# Lights.net
KiCad netlist of a schematic drawn in Altium Designer
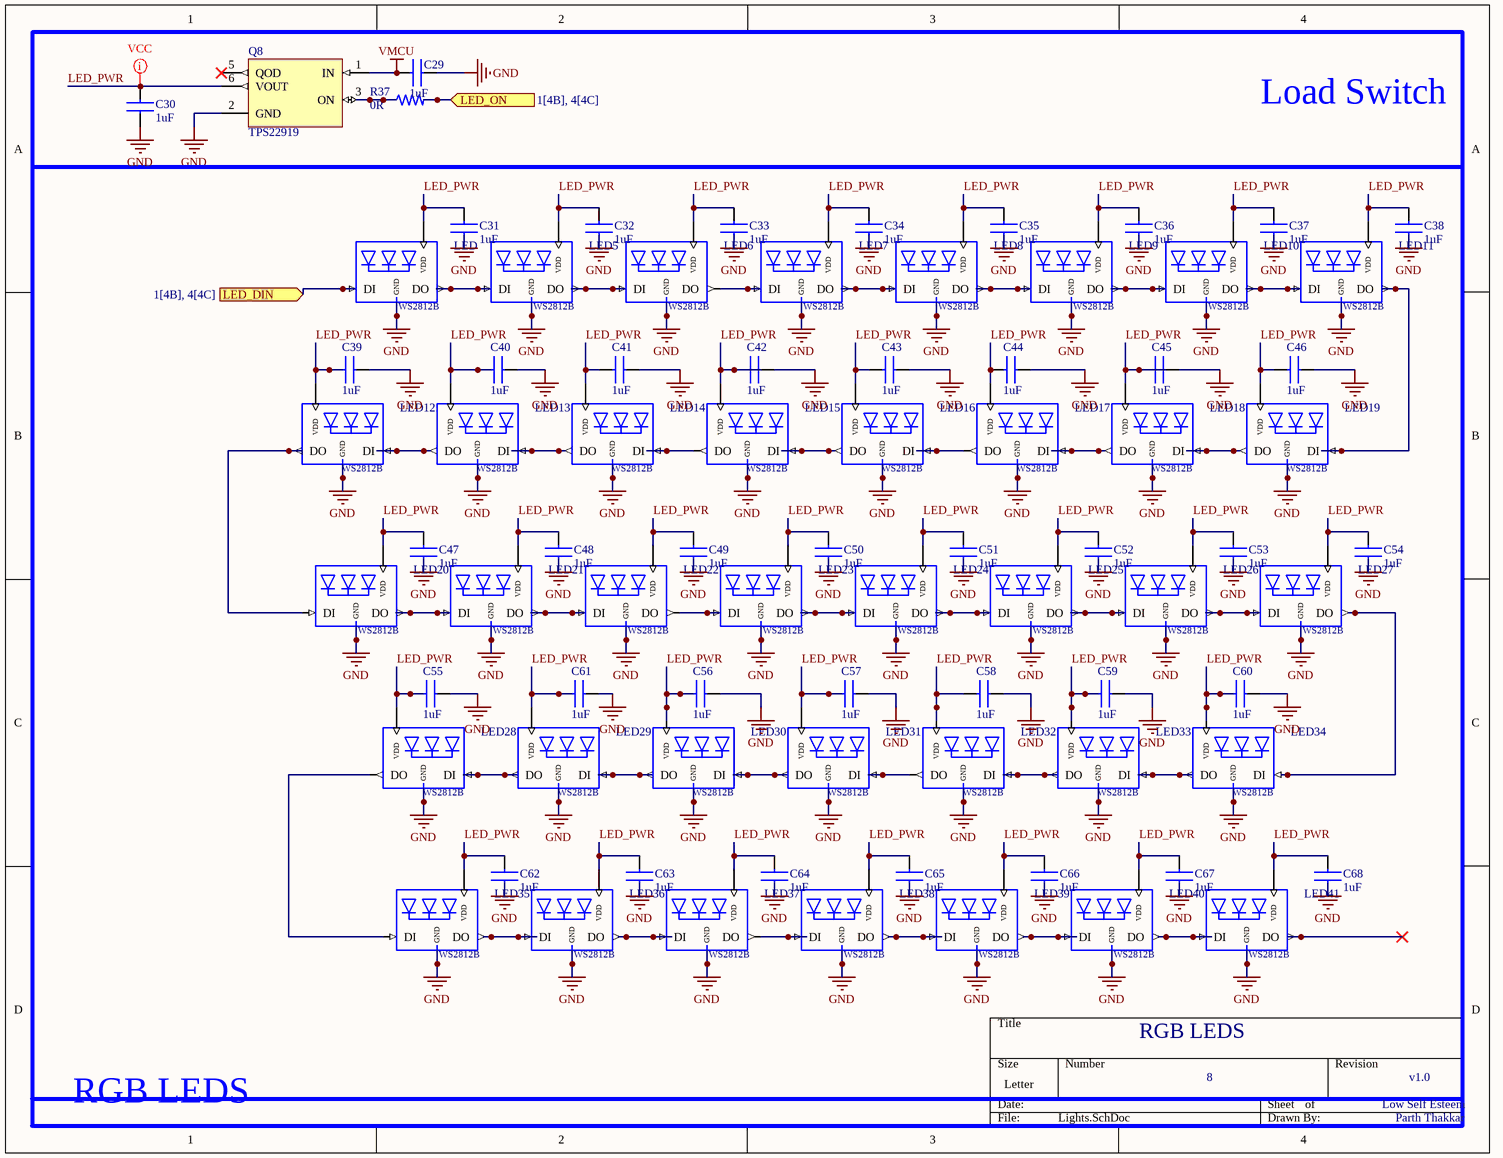
[diagram p0: Lights.SchDoc]

(export (version "E")
  (design (tool "Eeschema 10.0.6"))
  (components
    (comp (ref "C29")
      (value "1uF")
      (footprint "Capacitor 0603")
      (fields
        (field (name "MANUFACTURER") "Murata")
        (field (name "MANUFACTURER PART NUMBER") "GRM188R61A105KA61D")
        (field (name "Comment") "CAP 1uF 10V 0603")
      )
      (libsource (lib "Keyboard_parts") (part "CAP 1uF 10V 0603"))
    )
    (comp (ref "C30")
      (value "1uF")
      (footprint "CAPACITOR 0805")
      (description "Multilayer Ceramic Capacitor, 1 uF, 10 V, ± 20%, X5R, 0201 [0603 Metric]")
      (fields
        (field (name "MANUFACTURER") "Murata")
        (field (name "MANUFACTURER PART NUMBER") "GRM033R61A105ME15D")
      )
      (libsource (lib "Keyboard_parts") (part "CAP 47uF 10V 0805"))
    )
    (comp (ref "C31")
      (value "1uF")
      (footprint "Capacitor 0603")
      (fields
        (field (name "MANUFACTURER") "Murata")
        (field (name "MANUFACTURER PART NUMBER") "GRM188R61A105KA61D")
        (field (name "Comment") "CAP 1uF 10V 0603")
      )
      (libsource (lib "Keyboard_parts") (part "CAP 1uF 10V 0603"))
    )
    (comp (ref "C32")
      (value "1uF")
      (footprint "Capacitor 0603")
      (fields
        (field (name "MANUFACTURER") "Murata")
        (field (name "MANUFACTURER PART NUMBER") "GRM188R61A105KA61D")
        (field (name "Comment") "CAP 1uF 10V 0603")
      )
      (libsource (lib "Keyboard_parts") (part "CAP 1uF 10V 0603"))
    )
    (comp (ref "C33")
      (value "1uF")
      (footprint "Capacitor 0603")
      (fields
        (field (name "MANUFACTURER") "Murata")
        (field (name "MANUFACTURER PART NUMBER") "GRM188R61A105KA61D")
        (field (name "Comment") "CAP 1uF 10V 0603")
      )
      (libsource (lib "Keyboard_parts") (part "CAP 1uF 10V 0603"))
    )
    (comp (ref "C34")
      (value "1uF")
      (footprint "Capacitor 0603")
      (fields
        (field (name "MANUFACTURER") "Murata")
        (field (name "MANUFACTURER PART NUMBER") "GRM188R61A105KA61D")
        (field (name "Comment") "CAP 1uF 10V 0603")
      )
      (libsource (lib "Keyboard_parts") (part "CAP 1uF 10V 0603"))
    )
    (comp (ref "C35")
      (value "1uF")
      (footprint "Capacitor 0603")
      (fields
        (field (name "MANUFACTURER") "Murata")
        (field (name "MANUFACTURER PART NUMBER") "GRM188R61A105KA61D")
        (field (name "Comment") "CAP 1uF 10V 0603")
      )
      (libsource (lib "Keyboard_parts") (part "CAP 1uF 10V 0603"))
    )
    (comp (ref "C36")
      (value "1uF")
      (footprint "Capacitor 0603")
      (fields
        (field (name "MANUFACTURER") "Murata")
        (field (name "MANUFACTURER PART NUMBER") "GRM188R61A105KA61D")
        (field (name "Comment") "CAP 1uF 10V 0603")
      )
      (libsource (lib "Keyboard_parts") (part "CAP 1uF 10V 0603"))
    )
    (comp (ref "C37")
      (value "1uF")
      (footprint "Capacitor 0603")
      (fields
        (field (name "MANUFACTURER") "Murata")
        (field (name "MANUFACTURER PART NUMBER") "GRM188R61A105KA61D")
        (field (name "Comment") "CAP 1uF 10V 0603")
      )
      (libsource (lib "Keyboard_parts") (part "CAP 1uF 10V 0603"))
    )
    (comp (ref "C38")
      (value "1uF")
      (footprint "Capacitor 0603")
      (fields
        (field (name "MANUFACTURER") "Murata")
        (field (name "MANUFACTURER PART NUMBER") "GRM188R61A105KA61D")
        (field (name "Comment") "CAP 1uF 10V 0603")
      )
      (libsource (lib "Keyboard_parts") (part "CAP 1uF 10V 0603"))
    )
    (comp (ref "C39")
      (value "1uF")
      (footprint "Capacitor 0603")
      (fields
        (field (name "MANUFACTURER") "Murata")
        (field (name "MANUFACTURER PART NUMBER") "GRM188R61A105KA61D")
        (field (name "Comment") "CAP 1uF 10V 0603")
      )
      (libsource (lib "Keyboard_parts") (part "CAP 1uF 10V 0603"))
    )
    (comp (ref "C40")
      (value "1uF")
      (footprint "Capacitor 0603")
      (fields
        (field (name "MANUFACTURER") "Murata")
        (field (name "MANUFACTURER PART NUMBER") "GRM188R61A105KA61D")
        (field (name "Comment") "CAP 1uF 10V 0603")
      )
      (libsource (lib "Keyboard_parts") (part "CAP 1uF 10V 0603"))
    )
    (comp (ref "C41")
      (value "1uF")
      (footprint "Capacitor 0603")
      (fields
        (field (name "MANUFACTURER") "Murata")
        (field (name "MANUFACTURER PART NUMBER") "GRM188R61A105KA61D")
        (field (name "Comment") "CAP 1uF 10V 0603")
      )
      (libsource (lib "Keyboard_parts") (part "CAP 1uF 10V 0603"))
    )
    (comp (ref "C42")
      (value "1uF")
      (footprint "Capacitor 0603")
      (fields
        (field (name "MANUFACTURER") "Murata")
        (field (name "MANUFACTURER PART NUMBER") "GRM188R61A105KA61D")
        (field (name "Comment") "CAP 1uF 10V 0603")
      )
      (libsource (lib "Keyboard_parts") (part "CAP 1uF 10V 0603"))
    )
    (comp (ref "C43")
      (value "1uF")
      (footprint "Capacitor 0603")
      (fields
        (field (name "MANUFACTURER") "Murata")
        (field (name "MANUFACTURER PART NUMBER") "GRM188R61A105KA61D")
        (field (name "Comment") "CAP 1uF 10V 0603")
      )
      (libsource (lib "Keyboard_parts") (part "CAP 1uF 10V 0603"))
    )
    (comp (ref "C44")
      (value "1uF")
      (footprint "Capacitor 0603")
      (fields
        (field (name "MANUFACTURER") "Murata")
        (field (name "MANUFACTURER PART NUMBER") "GRM188R61A105KA61D")
        (field (name "Comment") "CAP 1uF 10V 0603")
      )
      (libsource (lib "Keyboard_parts") (part "CAP 1uF 10V 0603"))
    )
    (comp (ref "C45")
      (value "1uF")
      (footprint "Capacitor 0603")
      (fields
        (field (name "MANUFACTURER") "Murata")
        (field (name "MANUFACTURER PART NUMBER") "GRM188R61A105KA61D")
        (field (name "Comment") "CAP 1uF 10V 0603")
      )
      (libsource (lib "Keyboard_parts") (part "CAP 1uF 10V 0603"))
    )
    (comp (ref "C46")
      (value "1uF")
      (footprint "Capacitor 0603")
      (fields
        (field (name "MANUFACTURER") "Murata")
        (field (name "MANUFACTURER PART NUMBER") "GRM188R61A105KA61D")
        (field (name "Comment") "CAP 1uF 10V 0603")
      )
      (libsource (lib "Keyboard_parts") (part "CAP 1uF 10V 0603"))
    )
    (comp (ref "C47")
      (value "1uF")
      (footprint "Capacitor 0603")
      (fields
        (field (name "MANUFACTURER") "Murata")
        (field (name "MANUFACTURER PART NUMBER") "GRM188R61A105KA61D")
        (field (name "Comment") "CAP 1uF 10V 0603")
      )
      (libsource (lib "Keyboard_parts") (part "CAP 1uF 10V 0603"))
    )
    (comp (ref "C48")
      (value "1uF")
      (footprint "Capacitor 0603")
      (fields
        (field (name "MANUFACTURER") "Murata")
        (field (name "MANUFACTURER PART NUMBER") "GRM188R61A105KA61D")
        (field (name "Comment") "CAP 1uF 10V 0603")
      )
      (libsource (lib "Keyboard_parts") (part "CAP 1uF 10V 0603"))
    )
    (comp (ref "C49")
      (value "1uF")
      (footprint "Capacitor 0603")
      (fields
        (field (name "MANUFACTURER") "Murata")
        (field (name "MANUFACTURER PART NUMBER") "GRM188R61A105KA61D")
        (field (name "Comment") "CAP 1uF 10V 0603")
      )
      (libsource (lib "Keyboard_parts") (part "CAP 1uF 10V 0603"))
    )
    (comp (ref "C50")
      (value "1uF")
      (footprint "Capacitor 0603")
      (fields
        (field (name "MANUFACTURER") "Murata")
        (field (name "MANUFACTURER PART NUMBER") "GRM188R61A105KA61D")
        (field (name "Comment") "CAP 1uF 10V 0603")
      )
      (libsource (lib "Keyboard_parts") (part "CAP 1uF 10V 0603"))
    )
    (comp (ref "C51")
      (value "1uF")
      (footprint "Capacitor 0603")
      (fields
        (field (name "MANUFACTURER") "Murata")
        (field (name "MANUFACTURER PART NUMBER") "GRM188R61A105KA61D")
        (field (name "Comment") "CAP 1uF 10V 0603")
      )
      (libsource (lib "Keyboard_parts") (part "CAP 1uF 10V 0603"))
    )
    (comp (ref "C52")
      (value "1uF")
      (footprint "Capacitor 0603")
      (fields
        (field (name "MANUFACTURER") "Murata")
        (field (name "MANUFACTURER PART NUMBER") "GRM188R61A105KA61D")
        (field (name "Comment") "CAP 1uF 10V 0603")
      )
      (libsource (lib "Keyboard_parts") (part "CAP 1uF 10V 0603"))
    )
    (comp (ref "C53")
      (value "1uF")
      (footprint "Capacitor 0603")
      (fields
        (field (name "MANUFACTURER") "Murata")
        (field (name "MANUFACTURER PART NUMBER") "GRM188R61A105KA61D")
        (field (name "Comment") "CAP 1uF 10V 0603")
      )
      (libsource (lib "Keyboard_parts") (part "CAP 1uF 10V 0603"))
    )
    (comp (ref "C54")
      (value "1uF")
      (footprint "Capacitor 0603")
      (fields
        (field (name "MANUFACTURER") "Murata")
        (field (name "MANUFACTURER PART NUMBER") "GRM188R61A105KA61D")
        (field (name "Comment") "CAP 1uF 10V 0603")
      )
      (libsource (lib "Keyboard_parts") (part "CAP 1uF 10V 0603"))
    )
    (comp (ref "C55")
      (value "1uF")
      (footprint "Capacitor 0603")
      (fields
        (field (name "MANUFACTURER") "Murata")
        (field (name "MANUFACTURER PART NUMBER") "GRM188R61A105KA61D")
        (field (name "Comment") "CAP 1uF 10V 0603")
      )
      (libsource (lib "Keyboard_parts") (part "CAP 1uF 10V 0603"))
    )
    (comp (ref "C56")
      (value "1uF")
      (footprint "Capacitor 0603")
      (fields
        (field (name "MANUFACTURER") "Murata")
        (field (name "MANUFACTURER PART NUMBER") "GRM188R61A105KA61D")
        (field (name "Comment") "CAP 1uF 10V 0603")
      )
      (libsource (lib "Keyboard_parts") (part "CAP 1uF 10V 0603"))
    )
    (comp (ref "C57")
      (value "1uF")
      (footprint "Capacitor 0603")
      (fields
        (field (name "MANUFACTURER") "Murata")
        (field (name "MANUFACTURER PART NUMBER") "GRM188R61A105KA61D")
        (field (name "Comment") "CAP 1uF 10V 0603")
      )
      (libsource (lib "Keyboard_parts") (part "CAP 1uF 10V 0603"))
    )
    (comp (ref "C58")
      (value "1uF")
      (footprint "Capacitor 0603")
      (fields
        (field (name "MANUFACTURER") "Murata")
        (field (name "MANUFACTURER PART NUMBER") "GRM188R61A105KA61D")
        (field (name "Comment") "CAP 1uF 10V 0603")
      )
      (libsource (lib "Keyboard_parts") (part "CAP 1uF 10V 0603"))
    )
    (comp (ref "C59")
      (value "1uF")
      (footprint "Capacitor 0603")
      (fields
        (field (name "MANUFACTURER") "Murata")
        (field (name "MANUFACTURER PART NUMBER") "GRM188R61A105KA61D")
        (field (name "Comment") "CAP 1uF 10V 0603")
      )
      (libsource (lib "Keyboard_parts") (part "CAP 1uF 10V 0603"))
    )
    (comp (ref "C60")
      (value "1uF")
      (footprint "Capacitor 0603")
      (fields
        (field (name "MANUFACTURER") "Murata")
        (field (name "MANUFACTURER PART NUMBER") "GRM188R61A105KA61D")
        (field (name "Comment") "CAP 1uF 10V 0603")
      )
      (libsource (lib "Keyboard_parts") (part "CAP 1uF 10V 0603"))
    )
    (comp (ref "C61")
      (value "1uF")
      (footprint "Capacitor 0603")
      (fields
        (field (name "MANUFACTURER") "Murata")
        (field (name "MANUFACTURER PART NUMBER") "GRM188R61A105KA61D")
        (field (name "Comment") "CAP 1uF 10V 0603")
      )
      (libsource (lib "Keyboard_parts") (part "CAP 1uF 10V 0603"))
    )
    (comp (ref "C62")
      (value "1uF")
      (footprint "Capacitor 0603")
      (fields
        (field (name "MANUFACTURER") "Murata")
        (field (name "MANUFACTURER PART NUMBER") "GRM188R61A105KA61D")
        (field (name "Comment") "CAP 1uF 10V 0603")
      )
      (libsource (lib "Keyboard_parts") (part "CAP 1uF 10V 0603"))
    )
    (comp (ref "C63")
      (value "1uF")
      (footprint "Capacitor 0603")
      (fields
        (field (name "MANUFACTURER") "Murata")
        (field (name "MANUFACTURER PART NUMBER") "GRM188R61A105KA61D")
        (field (name "Comment") "CAP 1uF 10V 0603")
      )
      (libsource (lib "Keyboard_parts") (part "CAP 1uF 10V 0603"))
    )
    (comp (ref "C64")
      (value "1uF")
      (footprint "Capacitor 0603")
      (fields
        (field (name "MANUFACTURER") "Murata")
        (field (name "MANUFACTURER PART NUMBER") "GRM188R61A105KA61D")
        (field (name "Comment") "CAP 1uF 10V 0603")
      )
      (libsource (lib "Keyboard_parts") (part "CAP 1uF 10V 0603"))
    )
    (comp (ref "C65")
      (value "1uF")
      (footprint "Capacitor 0603")
      (fields
        (field (name "MANUFACTURER") "Murata")
        (field (name "MANUFACTURER PART NUMBER") "GRM188R61A105KA61D")
        (field (name "Comment") "CAP 1uF 10V 0603")
      )
      (libsource (lib "Keyboard_parts") (part "CAP 1uF 10V 0603"))
    )
    (comp (ref "C66")
      (value "1uF")
      (footprint "Capacitor 0603")
      (fields
        (field (name "MANUFACTURER") "Murata")
        (field (name "MANUFACTURER PART NUMBER") "GRM188R61A105KA61D")
        (field (name "Comment") "CAP 1uF 10V 0603")
      )
      (libsource (lib "Keyboard_parts") (part "CAP 1uF 10V 0603"))
    )
    (comp (ref "C67")
      (value "1uF")
      (footprint "Capacitor 0603")
      (fields
        (field (name "MANUFACTURER") "Murata")
        (field (name "MANUFACTURER PART NUMBER") "GRM188R61A105KA61D")
        (field (name "Comment") "CAP 1uF 10V 0603")
      )
      (libsource (lib "Keyboard_parts") (part "CAP 1uF 10V 0603"))
    )
    (comp (ref "C68")
      (value "1uF")
      (footprint "Capacitor 0603")
      (fields
        (field (name "MANUFACTURER") "Murata")
        (field (name "MANUFACTURER PART NUMBER") "GRM188R61A105KA61D")
        (field (name "Comment") "CAP 1uF 10V 0603")
      )
      (libsource (lib "Keyboard_parts") (part "CAP 1uF 10V 0603"))
    )
    (comp (ref "LED")
      (value "WS2812B")
      (footprint "WS2812B")
      (description "Raspberry Pi HAT _40 pin_ Wheeled Robotics Kit")
      (fields (field (name "MF") "SparkFun Electronics"))
      (libsource (lib "Keyboard_parts") (part "WS2812B"))
    )
    (comp (ref "LED5")
      (value "WS2812B")
      (footprint "WS2812B")
      (description "Raspberry Pi HAT _40 pin_ Wheeled Robotics Kit")
      (fields (field (name "MF") "SparkFun Electronics"))
      (libsource (lib "Keyboard_parts") (part "WS2812B"))
    )
    (comp (ref "LED6")
      (value "WS2812B")
      (footprint "WS2812B")
      (description "Raspberry Pi HAT _40 pin_ Wheeled Robotics Kit")
      (fields (field (name "MF") "SparkFun Electronics"))
      (libsource (lib "Keyboard_parts") (part "WS2812B"))
    )
    (comp (ref "LED7")
      (value "WS2812B")
      (footprint "WS2812B")
      (description "Raspberry Pi HAT _40 pin_ Wheeled Robotics Kit")
      (fields (field (name "MF") "SparkFun Electronics"))
      (libsource (lib "Keyboard_parts") (part "WS2812B"))
    )
    (comp (ref "LED8")
      (value "WS2812B")
      (footprint "WS2812B")
      (description "Raspberry Pi HAT _40 pin_ Wheeled Robotics Kit")
      (fields (field (name "MF") "SparkFun Electronics"))
      (libsource (lib "Keyboard_parts") (part "WS2812B"))
    )
    (comp (ref "LED9")
      (value "WS2812B")
      (footprint "WS2812B")
      (description "Raspberry Pi HAT _40 pin_ Wheeled Robotics Kit")
      (fields (field (name "MF") "SparkFun Electronics"))
      (libsource (lib "Keyboard_parts") (part "WS2812B"))
    )
    (comp (ref "LED10")
      (value "WS2812B")
      (footprint "WS2812B")
      (description "Raspberry Pi HAT _40 pin_ Wheeled Robotics Kit")
      (fields (field (name "MF") "SparkFun Electronics"))
      (libsource (lib "Keyboard_parts") (part "WS2812B"))
    )
    (comp (ref "LED11")
      (value "WS2812B")
      (footprint "WS2812B")
      (description "Raspberry Pi HAT _40 pin_ Wheeled Robotics Kit")
      (fields (field (name "MF") "SparkFun Electronics"))
      (libsource (lib "Keyboard_parts") (part "WS2812B"))
    )
    (comp (ref "LED12")
      (value "WS2812B")
      (footprint "WS2812B")
      (description "Raspberry Pi HAT _40 pin_ Wheeled Robotics Kit")
      (fields (field (name "MF") "SparkFun Electronics"))
      (libsource (lib "Keyboard_parts") (part "WS2812B"))
    )
    (comp (ref "LED13")
      (value "WS2812B")
      (footprint "WS2812B")
      (description "Raspberry Pi HAT _40 pin_ Wheeled Robotics Kit")
      (fields (field (name "MF") "SparkFun Electronics"))
      (libsource (lib "Keyboard_parts") (part "WS2812B"))
    )
    (comp (ref "LED14")
      (value "WS2812B")
      (footprint "WS2812B")
      (description "Raspberry Pi HAT _40 pin_ Wheeled Robotics Kit")
      (fields (field (name "MF") "SparkFun Electronics"))
      (libsource (lib "Keyboard_parts") (part "WS2812B"))
    )
    (comp (ref "LED15")
      (value "WS2812B")
      (footprint "WS2812B")
      (description "Raspberry Pi HAT _40 pin_ Wheeled Robotics Kit")
      (fields (field (name "MF") "SparkFun Electronics"))
      (libsource (lib "Keyboard_parts") (part "WS2812B"))
    )
    (comp (ref "LED16")
      (value "WS2812B")
      (footprint "WS2812B")
      (description "Raspberry Pi HAT _40 pin_ Wheeled Robotics Kit")
      (fields (field (name "MF") "SparkFun Electronics"))
      (libsource (lib "Keyboard_parts") (part "WS2812B"))
    )
    (comp (ref "LED17")
      (value "WS2812B")
      (footprint "WS2812B")
      (description "Raspberry Pi HAT _40 pin_ Wheeled Robotics Kit")
      (fields (field (name "MF") "SparkFun Electronics"))
      (libsource (lib "Keyboard_parts") (part "WS2812B"))
    )
    (comp (ref "LED18")
      (value "WS2812B")
      (footprint "WS2812B")
      (description "Raspberry Pi HAT _40 pin_ Wheeled Robotics Kit")
      (fields (field (name "MF") "SparkFun Electronics"))
      (libsource (lib "Keyboard_parts") (part "WS2812B"))
    )
    (comp (ref "LED19")
      (value "WS2812B")
      (footprint "WS2812B")
      (description "Raspberry Pi HAT _40 pin_ Wheeled Robotics Kit")
      (fields (field (name "MF") "SparkFun Electronics"))
      (libsource (lib "Keyboard_parts") (part "WS2812B"))
    )
    (comp (ref "LED20")
      (value "WS2812B")
      (footprint "WS2812B")
      (description "Raspberry Pi HAT _40 pin_ Wheeled Robotics Kit")
      (fields (field (name "MF") "SparkFun Electronics"))
      (libsource (lib "Keyboard_parts") (part "WS2812B"))
    )
    (comp (ref "LED21")
      (value "WS2812B")
      (footprint "WS2812B")
      (description "Raspberry Pi HAT _40 pin_ Wheeled Robotics Kit")
      (fields (field (name "MF") "SparkFun Electronics"))
      (libsource (lib "Keyboard_parts") (part "WS2812B"))
    )
    (comp (ref "LED22")
      (value "WS2812B")
      (footprint "WS2812B")
      (description "Raspberry Pi HAT _40 pin_ Wheeled Robotics Kit")
      (fields (field (name "MF") "SparkFun Electronics"))
      (libsource (lib "Keyboard_parts") (part "WS2812B"))
    )
    (comp (ref "LED23")
      (value "WS2812B")
      (footprint "WS2812B")
      (description "Raspberry Pi HAT _40 pin_ Wheeled Robotics Kit")
      (fields (field (name "MF") "SparkFun Electronics"))
      (libsource (lib "Keyboard_parts") (part "WS2812B"))
    )
    (comp (ref "LED24")
      (value "WS2812B")
      (footprint "WS2812B")
      (description "Raspberry Pi HAT _40 pin_ Wheeled Robotics Kit")
      (fields (field (name "MF") "SparkFun Electronics"))
      (libsource (lib "Keyboard_parts") (part "WS2812B"))
    )
    (comp (ref "LED25")
      (value "WS2812B")
      (footprint "WS2812B")
      (description "Raspberry Pi HAT _40 pin_ Wheeled Robotics Kit")
      (fields (field (name "MF") "SparkFun Electronics"))
      (libsource (lib "Keyboard_parts") (part "WS2812B"))
    )
    (comp (ref "LED26")
      (value "WS2812B")
      (footprint "WS2812B")
      (description "Raspberry Pi HAT _40 pin_ Wheeled Robotics Kit")
      (fields (field (name "MF") "SparkFun Electronics"))
      (libsource (lib "Keyboard_parts") (part "WS2812B"))
    )
    (comp (ref "LED27")
      (value "WS2812B")
      (footprint "WS2812B")
      (description "Raspberry Pi HAT _40 pin_ Wheeled Robotics Kit")
      (fields (field (name "MF") "SparkFun Electronics"))
      (libsource (lib "Keyboard_parts") (part "WS2812B"))
    )
    (comp (ref "LED28")
      (value "WS2812B")
      (footprint "WS2812B")
      (description "Raspberry Pi HAT _40 pin_ Wheeled Robotics Kit")
      (fields (field (name "MF") "SparkFun Electronics"))
      (libsource (lib "Keyboard_parts") (part "WS2812B"))
    )
    (comp (ref "LED29")
      (value "WS2812B")
      (footprint "WS2812B")
      (description "Raspberry Pi HAT _40 pin_ Wheeled Robotics Kit")
      (fields (field (name "MF") "SparkFun Electronics"))
      (libsource (lib "Keyboard_parts") (part "WS2812B"))
    )
    (comp (ref "LED30")
      (value "WS2812B")
      (footprint "WS2812B")
      (description "Raspberry Pi HAT _40 pin_ Wheeled Robotics Kit")
      (fields (field (name "MF") "SparkFun Electronics"))
      (libsource (lib "Keyboard_parts") (part "WS2812B"))
    )
    (comp (ref "LED31")
      (value "WS2812B")
      (footprint "WS2812B")
      (description "Raspberry Pi HAT _40 pin_ Wheeled Robotics Kit")
      (fields (field (name "MF") "SparkFun Electronics"))
      (libsource (lib "Keyboard_parts") (part "WS2812B"))
    )
    (comp (ref "LED32")
      (value "WS2812B")
      (footprint "WS2812B")
      (description "Raspberry Pi HAT _40 pin_ Wheeled Robotics Kit")
      (fields (field (name "MF") "SparkFun Electronics"))
      (libsource (lib "Keyboard_parts") (part "WS2812B"))
    )
    (comp (ref "LED33")
      (value "WS2812B")
      (footprint "WS2812B")
      (description "Raspberry Pi HAT _40 pin_ Wheeled Robotics Kit")
      (fields (field (name "MF") "SparkFun Electronics"))
      (libsource (lib "Keyboard_parts") (part "WS2812B"))
    )
    (comp (ref "LED34")
      (value "WS2812B")
      (footprint "WS2812B")
      (description "Raspberry Pi HAT _40 pin_ Wheeled Robotics Kit")
      (fields (field (name "MF") "SparkFun Electronics"))
      (libsource (lib "Keyboard_parts") (part "WS2812B"))
    )
    (comp (ref "LED35")
      (value "WS2812B")
      (footprint "WS2812B")
      (description "Raspberry Pi HAT _40 pin_ Wheeled Robotics Kit")
      (fields (field (name "MF") "SparkFun Electronics"))
      (libsource (lib "Keyboard_parts") (part "WS2812B"))
    )
    (comp (ref "LED36")
      (value "WS2812B")
      (footprint "WS2812B")
      (description "Raspberry Pi HAT _40 pin_ Wheeled Robotics Kit")
      (fields (field (name "MF") "SparkFun Electronics"))
      (libsource (lib "Keyboard_parts") (part "WS2812B"))
    )
    (comp (ref "LED37")
      (value "WS2812B")
      (footprint "WS2812B")
      (description "Raspberry Pi HAT _40 pin_ Wheeled Robotics Kit")
      (fields (field (name "MF") "SparkFun Electronics"))
      (libsource (lib "Keyboard_parts") (part "WS2812B"))
    )
    (comp (ref "LED38")
      (value "WS2812B")
      (footprint "WS2812B")
      (description "Raspberry Pi HAT _40 pin_ Wheeled Robotics Kit")
      (fields (field (name "MF") "SparkFun Electronics"))
      (libsource (lib "Keyboard_parts") (part "WS2812B"))
    )
    (comp (ref "LED39")
      (value "WS2812B")
      (footprint "WS2812B")
      (description "Raspberry Pi HAT _40 pin_ Wheeled Robotics Kit")
      (fields (field (name "MF") "SparkFun Electronics"))
      (libsource (lib "Keyboard_parts") (part "WS2812B"))
    )
    (comp (ref "LED40")
      (value "WS2812B")
      (footprint "WS2812B")
      (description "Raspberry Pi HAT _40 pin_ Wheeled Robotics Kit")
      (fields (field (name "MF") "SparkFun Electronics"))
      (libsource (lib "Keyboard_parts") (part "WS2812B"))
    )
    (comp (ref "LED41")
      (value "WS2812B")
      (footprint "WS2812B")
      (description "Raspberry Pi HAT _40 pin_ Wheeled Robotics Kit")
      (fields (field (name "MF") "SparkFun Electronics"))
      (libsource (lib "Keyboard_parts") (part "WS2812B"))
    )
    (comp (ref "Q8")
      (value "TPS22919")
      (footprint "TPS22919DCKR - Load SW")
      (description "Buffer/Inverter Based Peripheral Driver, 3A, PDSO6")
      (fields
        (field (name "MANUFACTURER") "Texas Instruments")
        (field (name "MANUFACTURER PART NUMBER") "TPS22919DCKT")
      )
      (libsource (lib "Keyboard_parts") (part "TPS22919"))
    )
    (comp (ref "R37")
      (value "0R")
      (footprint "Resistor 0402")
      (description "Metal Glaze/thick Film, 0.0625W, 0ohm, Surface Mount, 0402")
      (fields
        (field (name "MANUFACTURER") "Yageo")
        (field (name "MANUFACTURER PART NUMBER") "RC0402JR-070RL")
      )
      (libsource (lib "Keyboard_parts") (part "RES 0R 0402"))
    )
  )
  (nets
    (net (code "2") (name "/LED_DIN") (class "Default")
      (node (ref "LED") (pin "4-DIN") (pinfunction "DI_4-DIN") (pintype "input"))
    )
    (net (code "3") (name "/LED_ON") (class "Default")
      (node (ref "R37") (pin "2") (pinfunction "2_2") (pintype "passive"))
    )
    (net (code "4") (name "/LED_PWR") (class "Default")
      (node (ref "C30") (pin "1") (pinfunction "1_1") (pintype "passive"))
      (node (ref "C31") (pin "1") (pinfunction "1_1") (pintype "passive"))
      (node (ref "C32") (pin "1") (pinfunction "1_1") (pintype "passive"))
      (node (ref "C33") (pin "1") (pinfunction "1_1") (pintype "passive"))
      (node (ref "C34") (pin "1") (pinfunction "1_1") (pintype "passive"))
      (node (ref "C35") (pin "1") (pinfunction "1_1") (pintype "passive"))
      (node (ref "C36") (pin "1") (pinfunction "1_1") (pintype "passive"))
      (node (ref "C37") (pin "1") (pinfunction "1_1") (pintype "passive"))
      (node (ref "C38") (pin "1") (pinfunction "1_1") (pintype "passive"))
      (node (ref "C39") (pin "1") (pinfunction "1_1") (pintype "passive"))
      (node (ref "C40") (pin "1") (pinfunction "1_1") (pintype "passive"))
      (node (ref "C41") (pin "1") (pinfunction "1_1") (pintype "passive"))
      (node (ref "C42") (pin "1") (pinfunction "1_1") (pintype "passive"))
      (node (ref "C43") (pin "1") (pinfunction "1_1") (pintype "passive"))
      (node (ref "C44") (pin "1") (pinfunction "1_1") (pintype "passive"))
      (node (ref "C45") (pin "1") (pinfunction "1_1") (pintype "passive"))
      (node (ref "C46") (pin "1") (pinfunction "1_1") (pintype "passive"))
      (node (ref "C47") (pin "1") (pinfunction "1_1") (pintype "passive"))
      (node (ref "C48") (pin "1") (pinfunction "1_1") (pintype "passive"))
      (node (ref "C49") (pin "1") (pinfunction "1_1") (pintype "passive"))
      (node (ref "C50") (pin "1") (pinfunction "1_1") (pintype "passive"))
      (node (ref "C51") (pin "1") (pinfunction "1_1") (pintype "passive"))
      (node (ref "C52") (pin "1") (pinfunction "1_1") (pintype "passive"))
      (node (ref "C53") (pin "1") (pinfunction "1_1") (pintype "passive"))
      (node (ref "C54") (pin "1") (pinfunction "1_1") (pintype "passive"))
      (node (ref "C55") (pin "1") (pinfunction "1_1") (pintype "passive"))
      (node (ref "C56") (pin "1") (pinfunction "1_1") (pintype "passive"))
      (node (ref "C57") (pin "1") (pinfunction "1_1") (pintype "passive"))
      (node (ref "C58") (pin "1") (pinfunction "1_1") (pintype "passive"))
      (node (ref "C59") (pin "1") (pinfunction "1_1") (pintype "passive"))
      (node (ref "C60") (pin "1") (pinfunction "1_1") (pintype "passive"))
      (node (ref "C61") (pin "1") (pinfunction "1_1") (pintype "passive"))
      (node (ref "C62") (pin "1") (pinfunction "1_1") (pintype "passive"))
      (node (ref "C63") (pin "1") (pinfunction "1_1") (pintype "passive"))
      (node (ref "C64") (pin "1") (pinfunction "1_1") (pintype "passive"))
      (node (ref "C65") (pin "1") (pinfunction "1_1") (pintype "passive"))
      (node (ref "C66") (pin "1") (pinfunction "1_1") (pintype "passive"))
      (node (ref "C67") (pin "1") (pinfunction "1_1") (pintype "passive"))
      (node (ref "C68") (pin "1") (pinfunction "1_1") (pintype "passive"))
      (node (ref "LED") (pin "1-VDD") (pinfunction "VDD_1-VDD") (pintype "input"))
      (node (ref "LED10") (pin "1-VDD") (pinfunction "VDD_1-VDD") (pintype "input"))
      (node (ref "LED11") (pin "1-VDD") (pinfunction "VDD_1-VDD") (pintype "input"))
      (node (ref "LED12") (pin "1-VDD") (pinfunction "VDD_1-VDD") (pintype "input"))
      (node (ref "LED13") (pin "1-VDD") (pinfunction "VDD_1-VDD") (pintype "input"))
      (node (ref "LED14") (pin "1-VDD") (pinfunction "VDD_1-VDD") (pintype "input"))
      (node (ref "LED15") (pin "1-VDD") (pinfunction "VDD_1-VDD") (pintype "input"))
      (node (ref "LED16") (pin "1-VDD") (pinfunction "VDD_1-VDD") (pintype "input"))
      (node (ref "LED17") (pin "1-VDD") (pinfunction "VDD_1-VDD") (pintype "input"))
      (node (ref "LED18") (pin "1-VDD") (pinfunction "VDD_1-VDD") (pintype "input"))
      (node (ref "LED19") (pin "1-VDD") (pinfunction "VDD_1-VDD") (pintype "input"))
      (node (ref "LED20") (pin "1-VDD") (pinfunction "VDD_1-VDD") (pintype "input"))
      (node (ref "LED21") (pin "1-VDD") (pinfunction "VDD_1-VDD") (pintype "input"))
      (node (ref "LED22") (pin "1-VDD") (pinfunction "VDD_1-VDD") (pintype "input"))
      (node (ref "LED23") (pin "1-VDD") (pinfunction "VDD_1-VDD") (pintype "input"))
      (node (ref "LED24") (pin "1-VDD") (pinfunction "VDD_1-VDD") (pintype "input"))
      (node (ref "LED25") (pin "1-VDD") (pinfunction "VDD_1-VDD") (pintype "input"))
      (node (ref "LED26") (pin "1-VDD") (pinfunction "VDD_1-VDD") (pintype "input"))
      (node (ref "LED27") (pin "1-VDD") (pinfunction "VDD_1-VDD") (pintype "input"))
      (node (ref "LED28") (pin "1-VDD") (pinfunction "VDD_1-VDD") (pintype "input"))
      (node (ref "LED29") (pin "1-VDD") (pinfunction "VDD_1-VDD") (pintype "input"))
      (node (ref "LED30") (pin "1-VDD") (pinfunction "VDD_1-VDD") (pintype "input"))
      (node (ref "LED31") (pin "1-VDD") (pinfunction "VDD_1-VDD") (pintype "input"))
      (node (ref "LED32") (pin "1-VDD") (pinfunction "VDD_1-VDD") (pintype "input"))
      (node (ref "LED33") (pin "1-VDD") (pinfunction "VDD_1-VDD") (pintype "input"))
      (node (ref "LED34") (pin "1-VDD") (pinfunction "VDD_1-VDD") (pintype "input"))
      (node (ref "LED35") (pin "1-VDD") (pinfunction "VDD_1-VDD") (pintype "input"))
      (node (ref "LED36") (pin "1-VDD") (pinfunction "VDD_1-VDD") (pintype "input"))
      (node (ref "LED37") (pin "1-VDD") (pinfunction "VDD_1-VDD") (pintype "input"))
      (node (ref "LED38") (pin "1-VDD") (pinfunction "VDD_1-VDD") (pintype "input"))
      (node (ref "LED39") (pin "1-VDD") (pinfunction "VDD_1-VDD") (pintype "input"))
      (node (ref "LED40") (pin "1-VDD") (pinfunction "VDD_1-VDD") (pintype "input"))
      (node (ref "LED41") (pin "1-VDD") (pinfunction "VDD_1-VDD") (pintype "input"))
      (node (ref "LED5") (pin "1-VDD") (pinfunction "VDD_1-VDD") (pintype "input"))
      (node (ref "LED6") (pin "1-VDD") (pinfunction "VDD_1-VDD") (pintype "input"))
      (node (ref "LED7") (pin "1-VDD") (pinfunction "VDD_1-VDD") (pintype "input"))
      (node (ref "LED8") (pin "1-VDD") (pinfunction "VDD_1-VDD") (pintype "input"))
      (node (ref "LED9") (pin "1-VDD") (pinfunction "VDD_1-VDD") (pintype "input"))
      (node (ref "Q8") (pin "6") (pinfunction "VOUT_6") (pintype "output"))
    )
    (net (code "5") (name "GND") (class "Default")
      (node (ref "C29") (pin "2") (pinfunction "2_2") (pintype "passive"))
      (node (ref "C30") (pin "2") (pinfunction "2_2") (pintype "passive"))
      (node (ref "C31") (pin "2") (pinfunction "2_2") (pintype "passive"))
      (node (ref "C32") (pin "2") (pinfunction "2_2") (pintype "passive"))
      (node (ref "C33") (pin "2") (pinfunction "2_2") (pintype "passive"))
      (node (ref "C34") (pin "2") (pinfunction "2_2") (pintype "passive"))
      (node (ref "C35") (pin "2") (pinfunction "2_2") (pintype "passive"))
      (node (ref "C36") (pin "2") (pinfunction "2_2") (pintype "passive"))
      (node (ref "C37") (pin "2") (pinfunction "2_2") (pintype "passive"))
      (node (ref "C38") (pin "2") (pinfunction "2_2") (pintype "passive"))
      (node (ref "C39") (pin "2") (pinfunction "2_2") (pintype "passive"))
      (node (ref "C40") (pin "2") (pinfunction "2_2") (pintype "passive"))
      (node (ref "C41") (pin "2") (pinfunction "2_2") (pintype "passive"))
      (node (ref "C42") (pin "2") (pinfunction "2_2") (pintype "passive"))
      (node (ref "C43") (pin "2") (pinfunction "2_2") (pintype "passive"))
      (node (ref "C44") (pin "2") (pinfunction "2_2") (pintype "passive"))
      (node (ref "C45") (pin "2") (pinfunction "2_2") (pintype "passive"))
      (node (ref "C46") (pin "2") (pinfunction "2_2") (pintype "passive"))
      (node (ref "C47") (pin "2") (pinfunction "2_2") (pintype "passive"))
      (node (ref "C48") (pin "2") (pinfunction "2_2") (pintype "passive"))
      (node (ref "C49") (pin "2") (pinfunction "2_2") (pintype "passive"))
      (node (ref "C50") (pin "2") (pinfunction "2_2") (pintype "passive"))
      (node (ref "C51") (pin "2") (pinfunction "2_2") (pintype "passive"))
      (node (ref "C52") (pin "2") (pinfunction "2_2") (pintype "passive"))
      (node (ref "C53") (pin "2") (pinfunction "2_2") (pintype "passive"))
      (node (ref "C54") (pin "2") (pinfunction "2_2") (pintype "passive"))
      (node (ref "C55") (pin "2") (pinfunction "2_2") (pintype "passive"))
      (node (ref "C56") (pin "2") (pinfunction "2_2") (pintype "passive"))
      (node (ref "C57") (pin "2") (pinfunction "2_2") (pintype "passive"))
      (node (ref "C58") (pin "2") (pinfunction "2_2") (pintype "passive"))
      (node (ref "C59") (pin "2") (pinfunction "2_2") (pintype "passive"))
      (node (ref "C60") (pin "2") (pinfunction "2_2") (pintype "passive"))
      (node (ref "C61") (pin "2") (pinfunction "2_2") (pintype "passive"))
      (node (ref "C62") (pin "2") (pinfunction "2_2") (pintype "passive"))
      (node (ref "C63") (pin "2") (pinfunction "2_2") (pintype "passive"))
      (node (ref "C64") (pin "2") (pinfunction "2_2") (pintype "passive"))
      (node (ref "C65") (pin "2") (pinfunction "2_2") (pintype "passive"))
      (node (ref "C66") (pin "2") (pinfunction "2_2") (pintype "passive"))
      (node (ref "C67") (pin "2") (pinfunction "2_2") (pintype "passive"))
      (node (ref "C68") (pin "2") (pinfunction "2_2") (pintype "passive"))
      (node (ref "LED") (pin "3-GND") (pinfunction "GND_3-GND") (pintype "power_in"))
      (node (ref "LED10") (pin "3-GND") (pinfunction "GND_3-GND") (pintype "power_in"))
      (node (ref "LED11") (pin "3-GND") (pinfunction "GND_3-GND") (pintype "power_in"))
      (node (ref "LED12") (pin "3-GND") (pinfunction "GND_3-GND") (pintype "power_in"))
      (node (ref "LED13") (pin "3-GND") (pinfunction "GND_3-GND") (pintype "power_in"))
      (node (ref "LED14") (pin "3-GND") (pinfunction "GND_3-GND") (pintype "power_in"))
      (node (ref "LED15") (pin "3-GND") (pinfunction "GND_3-GND") (pintype "power_in"))
      (node (ref "LED16") (pin "3-GND") (pinfunction "GND_3-GND") (pintype "power_in"))
      (node (ref "LED17") (pin "3-GND") (pinfunction "GND_3-GND") (pintype "power_in"))
      (node (ref "LED18") (pin "3-GND") (pinfunction "GND_3-GND") (pintype "power_in"))
      (node (ref "LED19") (pin "3-GND") (pinfunction "GND_3-GND") (pintype "power_in"))
      (node (ref "LED20") (pin "3-GND") (pinfunction "GND_3-GND") (pintype "power_in"))
      (node (ref "LED21") (pin "3-GND") (pinfunction "GND_3-GND") (pintype "power_in"))
      (node (ref "LED22") (pin "3-GND") (pinfunction "GND_3-GND") (pintype "power_in"))
      (node (ref "LED23") (pin "3-GND") (pinfunction "GND_3-GND") (pintype "power_in"))
      (node (ref "LED24") (pin "3-GND") (pinfunction "GND_3-GND") (pintype "power_in"))
      (node (ref "LED25") (pin "3-GND") (pinfunction "GND_3-GND") (pintype "power_in"))
      (node (ref "LED26") (pin "3-GND") (pinfunction "GND_3-GND") (pintype "power_in"))
      (node (ref "LED27") (pin "3-GND") (pinfunction "GND_3-GND") (pintype "power_in"))
      (node (ref "LED28") (pin "3-GND") (pinfunction "GND_3-GND") (pintype "power_in"))
      (node (ref "LED29") (pin "3-GND") (pinfunction "GND_3-GND") (pintype "power_in"))
      (node (ref "LED30") (pin "3-GND") (pinfunction "GND_3-GND") (pintype "power_in"))
      (node (ref "LED31") (pin "3-GND") (pinfunction "GND_3-GND") (pintype "power_in"))
      (node (ref "LED32") (pin "3-GND") (pinfunction "GND_3-GND") (pintype "power_in"))
      (node (ref "LED33") (pin "3-GND") (pinfunction "GND_3-GND") (pintype "power_in"))
      (node (ref "LED34") (pin "3-GND") (pinfunction "GND_3-GND") (pintype "power_in"))
      (node (ref "LED35") (pin "3-GND") (pinfunction "GND_3-GND") (pintype "power_in"))
      (node (ref "LED36") (pin "3-GND") (pinfunction "GND_3-GND") (pintype "power_in"))
      (node (ref "LED37") (pin "3-GND") (pinfunction "GND_3-GND") (pintype "power_in"))
      (node (ref "LED38") (pin "3-GND") (pinfunction "GND_3-GND") (pintype "power_in"))
      (node (ref "LED39") (pin "3-GND") (pinfunction "GND_3-GND") (pintype "power_in"))
      (node (ref "LED40") (pin "3-GND") (pinfunction "GND_3-GND") (pintype "power_in"))
      (node (ref "LED41") (pin "3-GND") (pinfunction "GND_3-GND") (pintype "power_in"))
      (node (ref "LED5") (pin "3-GND") (pinfunction "GND_3-GND") (pintype "power_in"))
      (node (ref "LED6") (pin "3-GND") (pinfunction "GND_3-GND") (pintype "power_in"))
      (node (ref "LED7") (pin "3-GND") (pinfunction "GND_3-GND") (pintype "power_in"))
      (node (ref "LED8") (pin "3-GND") (pinfunction "GND_3-GND") (pintype "power_in"))
      (node (ref "LED9") (pin "3-GND") (pinfunction "GND_3-GND") (pintype "power_in"))
      (node (ref "Q8") (pin "2") (pinfunction "GND_2") (pintype "power_in"))
    )
    (net (code "6") (name "Net-(LED-DO)") (class "Default")
      (node (ref "LED") (pin "2-DOUT") (pinfunction "DO_2-DOUT") (pintype "output"))
      (node (ref "LED5") (pin "4-DIN") (pinfunction "DI_4-DIN") (pintype "input"))
    )
    (net (code "7") (name "Net-(LED5-DO)") (class "Default")
      (node (ref "LED5") (pin "2-DOUT") (pinfunction "DO_2-DOUT") (pintype "output"))
      (node (ref "LED6") (pin "4-DIN") (pinfunction "DI_4-DIN") (pintype "input"))
    )
    (net (code "8") (name "Net-(LED6-DO)") (class "Default")
      (node (ref "LED6") (pin "2-DOUT") (pinfunction "DO_2-DOUT") (pintype "output"))
      (node (ref "LED7") (pin "4-DIN") (pinfunction "DI_4-DIN") (pintype "input"))
    )
    (net (code "9") (name "Net-(LED7-DO)") (class "Default")
      (node (ref "LED7") (pin "2-DOUT") (pinfunction "DO_2-DOUT") (pintype "output"))
      (node (ref "LED8") (pin "4-DIN") (pinfunction "DI_4-DIN") (pintype "input"))
    )
    (net (code "10") (name "Net-(LED8-DO)") (class "Default")
      (node (ref "LED8") (pin "2-DOUT") (pinfunction "DO_2-DOUT") (pintype "output"))
      (node (ref "LED9") (pin "4-DIN") (pinfunction "DI_4-DIN") (pintype "input"))
    )
    (net (code "11") (name "Net-(LED10-DI)") (class "Default")
      (node (ref "LED10") (pin "4-DIN") (pinfunction "DI_4-DIN") (pintype "input"))
      (node (ref "LED9") (pin "2-DOUT") (pinfunction "DO_2-DOUT") (pintype "output"))
    )
    (net (code "12") (name "Net-(LED10-DO)") (class "Default")
      (node (ref "LED10") (pin "2-DOUT") (pinfunction "DO_2-DOUT") (pintype "output"))
      (node (ref "LED11") (pin "4-DIN") (pinfunction "DI_4-DIN") (pintype "input"))
    )
    (net (code "13") (name "Net-(LED11-DO)") (class "Default")
      (node (ref "LED11") (pin "2-DOUT") (pinfunction "DO_2-DOUT") (pintype "output"))
      (node (ref "LED19") (pin "4-DIN") (pinfunction "DI_4-DIN") (pintype "input"))
    )
    (net (code "14") (name "Net-(LED12-DI)") (class "Default")
      (node (ref "LED12") (pin "4-DIN") (pinfunction "DI_4-DIN") (pintype "input"))
      (node (ref "LED13") (pin "2-DOUT") (pinfunction "DO_2-DOUT") (pintype "output"))
    )
    (net (code "15") (name "Net-(LED12-DO)") (class "Default")
      (node (ref "LED12") (pin "2-DOUT") (pinfunction "DO_2-DOUT") (pintype "output"))
      (node (ref "LED20") (pin "4-DIN") (pinfunction "DI_4-DIN") (pintype "input"))
    )
    (net (code "16") (name "Net-(LED13-DI)") (class "Default")
      (node (ref "LED13") (pin "4-DIN") (pinfunction "DI_4-DIN") (pintype "input"))
      (node (ref "LED14") (pin "2-DOUT") (pinfunction "DO_2-DOUT") (pintype "output"))
    )
    (net (code "17") (name "Net-(LED14-DI)") (class "Default")
      (node (ref "LED14") (pin "4-DIN") (pinfunction "DI_4-DIN") (pintype "input"))
      (node (ref "LED15") (pin "2-DOUT") (pinfunction "DO_2-DOUT") (pintype "output"))
    )
    (net (code "18") (name "Net-(LED15-DI)") (class "Default")
      (node (ref "LED15") (pin "4-DIN") (pinfunction "DI_4-DIN") (pintype "input"))
      (node (ref "LED16") (pin "2-DOUT") (pinfunction "DO_2-DOUT") (pintype "output"))
    )
    (net (code "19") (name "Net-(LED16-DI)") (class "Default")
      (node (ref "LED16") (pin "4-DIN") (pinfunction "DI_4-DIN") (pintype "input"))
      (node (ref "LED17") (pin "2-DOUT") (pinfunction "DO_2-DOUT") (pintype "output"))
    )
    (net (code "20") (name "Net-(LED17-DI)") (class "Default")
      (node (ref "LED17") (pin "4-DIN") (pinfunction "DI_4-DIN") (pintype "input"))
      (node (ref "LED18") (pin "2-DOUT") (pinfunction "DO_2-DOUT") (pintype "output"))
    )
    (net (code "21") (name "Net-(LED18-DI)") (class "Default")
      (node (ref "LED18") (pin "4-DIN") (pinfunction "DI_4-DIN") (pintype "input"))
      (node (ref "LED19") (pin "2-DOUT") (pinfunction "DO_2-DOUT") (pintype "output"))
    )
    (net (code "22") (name "Net-(LED20-DO)") (class "Default")
      (node (ref "LED20") (pin "2-DOUT") (pinfunction "DO_2-DOUT") (pintype "output"))
      (node (ref "LED21") (pin "4-DIN") (pinfunction "DI_4-DIN") (pintype "input"))
    )
    (net (code "23") (name "Net-(LED21-DO)") (class "Default")
      (node (ref "LED21") (pin "2-DOUT") (pinfunction "DO_2-DOUT") (pintype "output"))
      (node (ref "LED22") (pin "4-DIN") (pinfunction "DI_4-DIN") (pintype "input"))
    )
    (net (code "24") (name "Net-(LED22-DO)") (class "Default")
      (node (ref "LED22") (pin "2-DOUT") (pinfunction "DO_2-DOUT") (pintype "output"))
      (node (ref "LED23") (pin "4-DIN") (pinfunction "DI_4-DIN") (pintype "input"))
    )
    (net (code "25") (name "Net-(LED23-DO)") (class "Default")
      (node (ref "LED23") (pin "2-DOUT") (pinfunction "DO_2-DOUT") (pintype "output"))
      (node (ref "LED24") (pin "4-DIN") (pinfunction "DI_4-DIN") (pintype "input"))
    )
    (net (code "26") (name "Net-(LED24-DO)") (class "Default")
      (node (ref "LED24") (pin "2-DOUT") (pinfunction "DO_2-DOUT") (pintype "output"))
      (node (ref "LED25") (pin "4-DIN") (pinfunction "DI_4-DIN") (pintype "input"))
    )
    (net (code "27") (name "Net-(LED25-DO)") (class "Default")
      (node (ref "LED25") (pin "2-DOUT") (pinfunction "DO_2-DOUT") (pintype "output"))
      (node (ref "LED26") (pin "4-DIN") (pinfunction "DI_4-DIN") (pintype "input"))
    )
    (net (code "28") (name "Net-(LED26-DO)") (class "Default")
      (node (ref "LED26") (pin "2-DOUT") (pinfunction "DO_2-DOUT") (pintype "output"))
      (node (ref "LED27") (pin "4-DIN") (pinfunction "DI_4-DIN") (pintype "input"))
    )
    (net (code "29") (name "Net-(LED27-DO)") (class "Default")
      (node (ref "LED27") (pin "2-DOUT") (pinfunction "DO_2-DOUT") (pintype "output"))
      (node (ref "LED34") (pin "4-DIN") (pinfunction "DI_4-DIN") (pintype "input"))
    )
    (net (code "30") (name "Net-(LED28-DI)") (class "Default")
      (node (ref "LED28") (pin "4-DIN") (pinfunction "DI_4-DIN") (pintype "input"))
      (node (ref "LED29") (pin "2-DOUT") (pinfunction "DO_2-DOUT") (pintype "output"))
    )
    (net (code "31") (name "Net-(LED28-DO)") (class "Default")
      (node (ref "LED28") (pin "2-DOUT") (pinfunction "DO_2-DOUT") (pintype "output"))
      (node (ref "LED35") (pin "4-DIN") (pinfunction "DI_4-DIN") (pintype "input"))
    )
    (net (code "32") (name "Net-(LED29-DI)") (class "Default")
      (node (ref "LED29") (pin "4-DIN") (pinfunction "DI_4-DIN") (pintype "input"))
      (node (ref "LED30") (pin "2-DOUT") (pinfunction "DO_2-DOUT") (pintype "output"))
    )
    (net (code "33") (name "Net-(LED30-DI)") (class "Default")
      (node (ref "LED30") (pin "4-DIN") (pinfunction "DI_4-DIN") (pintype "input"))
      (node (ref "LED31") (pin "2-DOUT") (pinfunction "DO_2-DOUT") (pintype "output"))
    )
    (net (code "34") (name "Net-(LED31-DI)") (class "Default")
      (node (ref "LED31") (pin "4-DIN") (pinfunction "DI_4-DIN") (pintype "input"))
      (node (ref "LED32") (pin "2-DOUT") (pinfunction "DO_2-DOUT") (pintype "output"))
    )
    (net (code "35") (name "Net-(LED32-DI)") (class "Default")
      (node (ref "LED32") (pin "4-DIN") (pinfunction "DI_4-DIN") (pintype "input"))
      (node (ref "LED33") (pin "2-DOUT") (pinfunction "DO_2-DOUT") (pintype "output"))
    )
    (net (code "36") (name "Net-(LED33-DI)") (class "Default")
      (node (ref "LED33") (pin "4-DIN") (pinfunction "DI_4-DIN") (pintype "input"))
      (node (ref "LED34") (pin "2-DOUT") (pinfunction "DO_2-DOUT") (pintype "output"))
    )
    (net (code "37") (name "Net-(LED35-DO)") (class "Default")
      (node (ref "LED35") (pin "2-DOUT") (pinfunction "DO_2-DOUT") (pintype "output"))
      (node (ref "LED36") (pin "4-DIN") (pinfunction "DI_4-DIN") (pintype "input"))
    )
    (net (code "38") (name "Net-(LED36-DO)") (class "Default")
      (node (ref "LED36") (pin "2-DOUT") (pinfunction "DO_2-DOUT") (pintype "output"))
      (node (ref "LED37") (pin "4-DIN") (pinfunction "DI_4-DIN") (pintype "input"))
    )
    (net (code "39") (name "Net-(LED37-DO)") (class "Default")
      (node (ref "LED37") (pin "2-DOUT") (pinfunction "DO_2-DOUT") (pintype "output"))
      (node (ref "LED38") (pin "4-DIN") (pinfunction "DI_4-DIN") (pintype "input"))
    )
    (net (code "40") (name "Net-(LED38-DO)") (class "Default")
      (node (ref "LED38") (pin "2-DOUT") (pinfunction "DO_2-DOUT") (pintype "output"))
      (node (ref "LED39") (pin "4-DIN") (pinfunction "DI_4-DIN") (pintype "input"))
    )
    (net (code "41") (name "Net-(LED39-DO)") (class "Default")
      (node (ref "LED39") (pin "2-DOUT") (pinfunction "DO_2-DOUT") (pintype "output"))
      (node (ref "LED40") (pin "4-DIN") (pinfunction "DI_4-DIN") (pintype "input"))
    )
    (net (code "42") (name "Net-(LED40-DO)") (class "Default")
      (node (ref "LED40") (pin "2-DOUT") (pinfunction "DO_2-DOUT") (pintype "output"))
      (node (ref "LED41") (pin "4-DIN") (pinfunction "DI_4-DIN") (pintype "input"))
    )
    (net (code "43") (name "Net-(Q8-ON)") (class "Default")
      (node (ref "Q8") (pin "3") (pinfunction "ON_3") (pintype "bidirectional"))
      (node (ref "R37") (pin "1") (pinfunction "1_1") (pintype "passive"))
    )
    (net (code "44") (name "VMCU") (class "Default")
      (node (ref "C29") (pin "1") (pinfunction "1_1") (pintype "passive"))
      (node (ref "Q8") (pin "1") (pinfunction "IN_1") (pintype "input"))
    )
    (net (code "45") (name "unconnected-(LED41-DO-Pad2-DOUT)") (class "Default")
      (node (ref "LED41") (pin "2-DOUT") (pinfunction "DO_2-DOUT") (pintype "output+no_connect"))
    )
    (net (code "46") (name "unconnected-(Q8-QOD-Pad5)") (class "Default")
      (node (ref "Q8") (pin "5") (pinfunction "QOD_5") (pintype "output+no_connect"))
    )
  )
)
